# placa.net
KiCad netlist of a schematic drawn in EAGLE
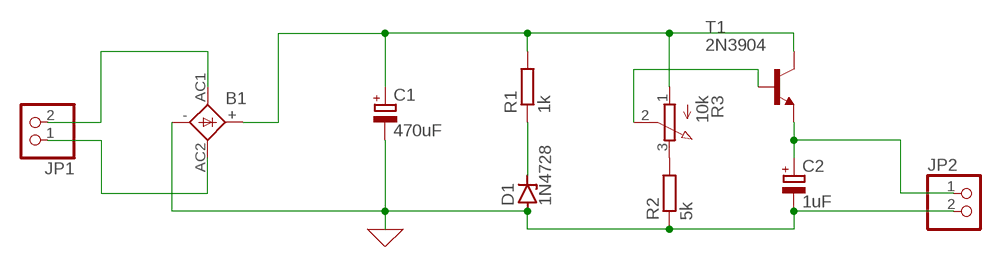
[diagram p0: schematic, sheet 1]

(export (version "E")
  (design (tool "Eeschema 10.0.6"))
  (components
    (comp (ref "B1")
      (value "1KAB")
      (footprint "eagle-import:1KAB")
      (libsource (lib "eagle-import") (part "1KAB"))
    )
    (comp (ref "C1")
      (value "470uF")
      (footprint "eagle-import:E5-10,5")
      (libsource (lib "eagle-import") (part "CPOL-EUE5-10.5"))
    )
    (comp (ref "C2")
      (value "1uF")
      (footprint "eagle-import:E5-10,5")
      (libsource (lib "eagle-import") (part "CPOL-EUE5-10.5"))
    )
    (comp (ref "D1")
      (value "1N4728")
      (footprint "eagle-import:DO41Z10")
      (libsource (lib "eagle-import") (part "1N4728"))
    )
    (comp (ref "JP1")
      (value "PINHD-1X2")
      (footprint "eagle-import:1X02")
      (libsource (lib "eagle-import") (part "PINHD-1X2"))
    )
    (comp (ref "JP2")
      (value "PINHD-1X2")
      (footprint "eagle-import:1X02")
      (libsource (lib "eagle-import") (part "PINHD-1X2"))
    )
    (comp (ref "R1")
      (value "1k")
      (footprint "eagle-import:0204_7")
      (libsource (lib "eagle-import") (part "R-EU_0204/7"))
    )
    (comp (ref "R2")
      (value "5k")
      (footprint "eagle-import:0204_7")
      (libsource (lib "eagle-import") (part "R-EU_0204/7"))
    )
    (comp (ref "R3")
      (value "10k")
      (footprint "eagle-import:3RP_1610N")
      (libsource (lib "eagle-import") (part "3RP/1610N"))
    )
    (comp (ref "T1")
      (value "2N3904")
      (footprint "eagle-import:TO92")
      (libsource (lib "eagle-import") (part "2N3904"))
    )
  )
  (nets
    (net (code "1") (name "GND") (class "Default")
      (node (ref "B1") (pin "-") (pinfunction "-_-") (pintype "passive"))
      (node (ref "C1") (pin "-") (pinfunction "-_-") (pintype "passive"))
      (node (ref "C2") (pin "-") (pinfunction "-_-") (pintype "passive"))
      (node (ref "D1") (pin "A") (pinfunction "A_A") (pintype "passive"))
      (node (ref "JP2") (pin "2") (pinfunction "2_2") (pintype "passive"))
      (node (ref "R2") (pin "1") (pinfunction "1_1") (pintype "passive"))
    )
    (net (code "2") (name "Net-(B1-PadAC1)") (class "Default")
      (node (ref "B1") (pin "AC1") (pinfunction "AC1_AC1") (pintype "passive"))
      (node (ref "JP1") (pin "2") (pinfunction "2_2") (pintype "passive"))
    )
    (net (code "3") (name "Net-(B1-PadAC2)") (class "Default")
      (node (ref "B1") (pin "AC2") (pinfunction "AC2_AC2") (pintype "passive"))
      (node (ref "JP1") (pin "1") (pinfunction "1_1") (pintype "passive"))
    )
    (net (code "4") (name "Net-(D1-PadC)") (class "Default")
      (node (ref "D1") (pin "C") (pinfunction "C_C") (pintype "passive"))
      (node (ref "R1") (pin "1") (pinfunction "1_1") (pintype "passive"))
    )
    (net (code "5") (name "Net-(R3-A)") (class "Default")
      (node (ref "B1") (pin "+") (pinfunction "+_+") (pintype "passive"))
      (node (ref "C1") (pin "+") (pinfunction "+_+") (pintype "passive"))
      (node (ref "R1") (pin "2") (pinfunction "2_2") (pintype "passive"))
      (node (ref "R3") (pin "1") (pinfunction "A_1") (pintype "passive"))
      (node (ref "T1") (pin "1") (pinfunction "C_1") (pintype "passive"))
    )
    (net (code "6") (name "Net-(R3-E)") (class "Default")
      (node (ref "R2") (pin "2") (pinfunction "2_2") (pintype "passive"))
      (node (ref "R3") (pin "3") (pinfunction "E_3") (pintype "passive"))
    )
    (net (code "7") (name "Net-(R3-S)") (class "Default")
      (node (ref "R3") (pin "2") (pinfunction "S_2") (pintype "passive"))
      (node (ref "T1") (pin "2") (pinfunction "B_2") (pintype "passive"))
    )
    (net (code "8") (name "Net-(T1-E)") (class "Default")
      (node (ref "C2") (pin "+") (pinfunction "+_+") (pintype "passive"))
      (node (ref "JP2") (pin "1") (pinfunction "1_1") (pintype "passive"))
      (node (ref "T1") (pin "3") (pinfunction "E_3") (pintype "passive"))
    )
  )
)
